# FRAM.net
KiCad netlist of a schematic drawn in Altium Designer
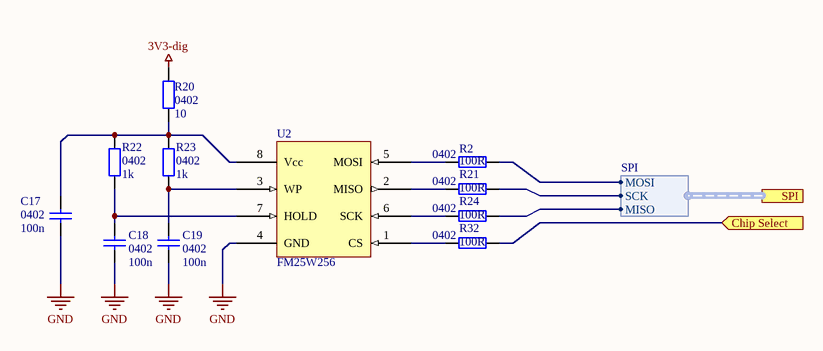
[diagram p0: FRAM.SchDoc]

(export (version "E")
  (design (tool "Eeschema 10.0.6"))
  (components
    (comp (ref "C17")
      (value "0402")
      (footprint "SMD_Capacitor_0402")
      (description "Capacitor")
      (fields (field (name "ALTIUM_VALUE") "100n") (field (name "PUBLISHER") "Altium Limited"))
      (libsource (lib "Miscellaneous Devices") (part "Cap"))
    )
    (comp (ref "C18")
      (value "0402")
      (footprint "SMD_Capacitor_0402")
      (description "Capacitor")
      (fields (field (name "ALTIUM_VALUE") "100n") (field (name "PUBLISHER") "Altium Limited"))
      (libsource (lib "Miscellaneous Devices") (part "Cap"))
    )
    (comp (ref "C19")
      (value "0402")
      (footprint "SMD_Capacitor_0402")
      (description "Capacitor")
      (fields (field (name "ALTIUM_VALUE") "100n") (field (name "PUBLISHER") "Altium Limited"))
      (libsource (lib "Miscellaneous Devices") (part "Cap"))
    )
    (comp (ref "R2")
      (value "0402")
      (footprint "SMD_Resistor_0402")
      (description "Resistor")
      (fields (field (name "ALTIUM_VALUE") "100R") (field (name "PUBLISHER") "Altium Limited"))
      (libsource (lib "") (part "Res2_1"))
    )
    (comp (ref "R20")
      (value "0402")
      (footprint "SMD_Resistor_0402")
      (description "Resistor")
      (fields (field (name "ALTIUM_VALUE") "10") (field (name "PUBLISHER") "Altium Limited"))
      (libsource (lib "Miscellaneous Devices") (part "Res2"))
    )
    (comp (ref "R21")
      (value "0402")
      (footprint "SMD_Resistor_0402")
      (description "Resistor")
      (fields (field (name "ALTIUM_VALUE") "100R") (field (name "PUBLISHER") "Altium Limited"))
      (libsource (lib "") (part "Res2_1"))
    )
    (comp (ref "R22")
      (value "0402")
      (footprint "SMD_Resistor_0402")
      (description "Resistor")
      (fields (field (name "ALTIUM_VALUE") "1k") (field (name "PUBLISHER") "Altium Limited"))
      (libsource (lib "Miscellaneous Devices") (part "Res2"))
    )
    (comp (ref "R23")
      (value "0402")
      (footprint "SMD_Resistor_0402")
      (description "Resistor")
      (fields (field (name "ALTIUM_VALUE") "1k") (field (name "PUBLISHER") "Altium Limited"))
      (libsource (lib "Miscellaneous Devices") (part "Res2"))
    )
    (comp (ref "R24")
      (value "0402")
      (footprint "SMD_Resistor_0402")
      (description "Resistor")
      (fields (field (name "ALTIUM_VALUE") "100R") (field (name "PUBLISHER") "Altium Limited"))
      (libsource (lib "") (part "Res2_1"))
    )
    (comp (ref "R32")
      (value "0402")
      (footprint "SMD_Resistor_0402")
      (description "Resistor")
      (fields (field (name "ALTIUM_VALUE") "100R") (field (name "PUBLISHER") "Altium Limited"))
      (libsource (lib "") (part "Res2_1"))
    )
    (comp (ref "U2")
      (value "FM25W256")
      (footprint "SOIC-8-N")
      (description "256Kb (8k x 32) SPI F-RAM")
      (libsource (lib "microcircuits_miscellaneous") (part "FM25W256"))
    )
  )
  (nets
    (net (code "2") (name "/Chip Select") (class "Default")
      (node (ref "R32") (pin "1") (pinfunction "1_1") (pintype "passive"))
    )
    (net (code "3") (name "/MISO") (class "Default")
      (node (ref "R24") (pin "1") (pinfunction "1_1") (pintype "passive"))
    )
    (net (code "4") (name "/MOSI") (class "Default")
      (node (ref "R2") (pin "1") (pinfunction "1_1") (pintype "passive"))
    )
    (net (code "5") (name "/SCK") (class "Default")
      (node (ref "R21") (pin "1") (pinfunction "1_1") (pintype "passive"))
    )
    (net (code "7") (name "3V3-dig") (class "Default")
      (node (ref "R20") (pin "2") (pinfunction "2_2") (pintype "passive"))
    )
    (net (code "8") (name "GND") (class "Default")
      (node (ref "C17") (pin "2") (pinfunction "2_2") (pintype "passive"))
      (node (ref "C18") (pin "2") (pinfunction "2_2") (pintype "passive"))
      (node (ref "C19") (pin "2") (pinfunction "2_2") (pintype "passive"))
      (node (ref "U2") (pin "4") (pinfunction "GND_4") (pintype "power_in"))
    )
    (net (code "9") (name "Net-(U2-CS)") (class "Default")
      (node (ref "R32") (pin "2") (pinfunction "2_2") (pintype "passive"))
      (node (ref "U2") (pin "1") (pinfunction "CS_1") (pintype "input"))
    )
    (net (code "10") (name "Net-(U2-HOLD)") (class "Default")
      (node (ref "C18") (pin "1") (pinfunction "1_1") (pintype "passive"))
      (node (ref "R22") (pin "1") (pinfunction "1_1") (pintype "passive"))
      (node (ref "U2") (pin "7") (pinfunction "HOLD_7") (pintype "input"))
    )
    (net (code "11") (name "Net-(U2-MISO)") (class "Default")
      (node (ref "R21") (pin "2") (pinfunction "2_2") (pintype "passive"))
      (node (ref "U2") (pin "2") (pinfunction "MISO_2") (pintype "output"))
    )
    (net (code "12") (name "Net-(U2-MOSI)") (class "Default")
      (node (ref "R2") (pin "2") (pinfunction "2_2") (pintype "passive"))
      (node (ref "U2") (pin "5") (pinfunction "MOSI_5") (pintype "input"))
    )
    (net (code "13") (name "Net-(U2-SCK)") (class "Default")
      (node (ref "R24") (pin "2") (pinfunction "2_2") (pintype "passive"))
      (node (ref "U2") (pin "6") (pinfunction "SCK_6") (pintype "input"))
    )
    (net (code "14") (name "Net-(U2-Vcc)") (class "Default")
      (node (ref "C17") (pin "1") (pinfunction "1_1") (pintype "passive"))
      (node (ref "R20") (pin "1") (pinfunction "1_1") (pintype "passive"))
      (node (ref "R22") (pin "2") (pinfunction "2_2") (pintype "passive"))
      (node (ref "R23") (pin "2") (pinfunction "2_2") (pintype "passive"))
      (node (ref "U2") (pin "8") (pinfunction "Vcc_8") (pintype "power_in"))
    )
    (net (code "15") (name "Net-(U2-WP)") (class "Default")
      (node (ref "C19") (pin "1") (pinfunction "1_1") (pintype "passive"))
      (node (ref "R23") (pin "1") (pinfunction "1_1") (pintype "passive"))
      (node (ref "U2") (pin "3") (pinfunction "WP_3") (pintype "input"))
    )
  )
)
